# PWR_MCU.net
KiCad netlist of a schematic drawn in Altium Designer
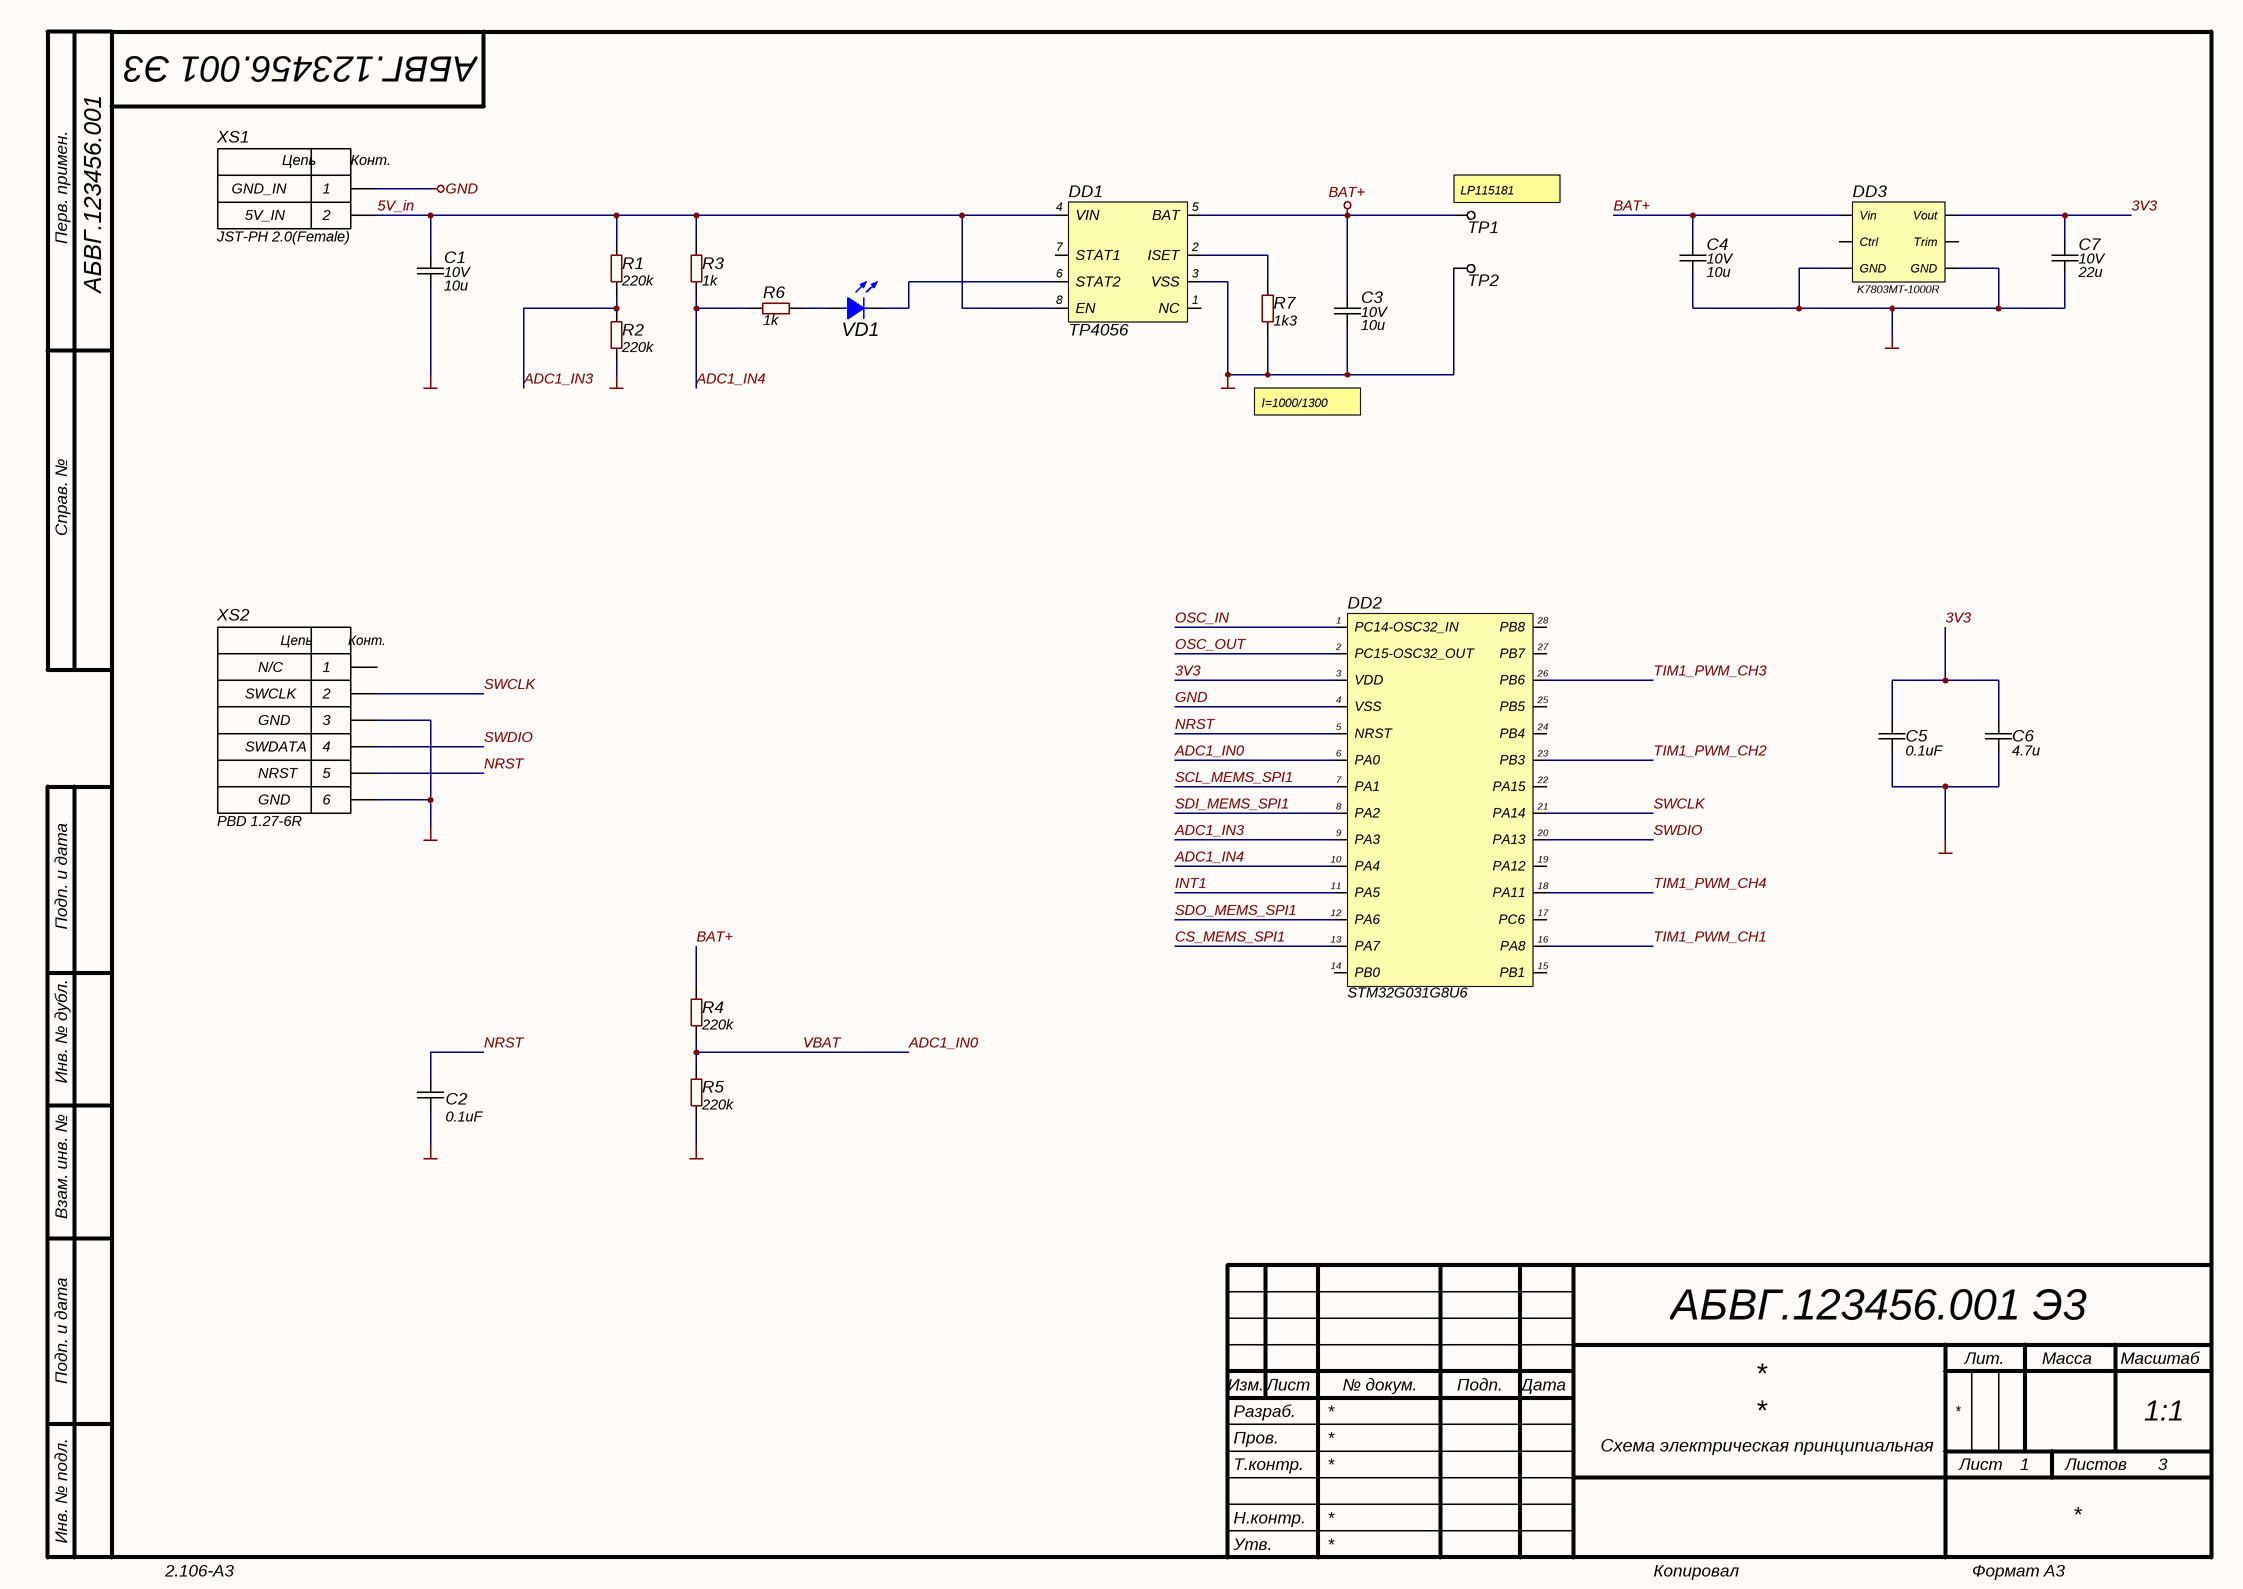
[diagram p0: PWR_MCU.SchDoc]

(export (version "E")
  (design (tool "Eeschema 10.0.6"))
  (components
    (comp (ref "C1")
      (value "10u")
      (footprint "CAP: 0603")
      (description "Capacitor")
      (fields
        (field (name "MANUFACTURER") "Yageo")
        (field (name "PARTNUMBER") "CC0603KRX7R7BB104")
        (field (name "VOLTAGE") "10V")
      )
      (libsource (lib "capacitor") (part "Ceramic_0603"))
    )
    (comp (ref "C2")
      (value "0.1uF")
      (footprint "CAP: 0603")
      (fields
        (field (name "MANUFACTURER") "Yageo")
        (field (name "PARTNUMBER") "CC0603KRX7R7BB104")
        (field (name "VALUEMANUFACTURERPARTNUMBER") "Ceramic capacitor, 0.1uF, X7R, ±10%, 16V, 0603, -55...+125°C")
      )
      (libsource (lib "capacitor") (part "Ceramic_0603"))
    )
    (comp (ref "C3")
      (value "10u")
      (footprint "CAP: 0603")
      (description "Capacitor")
      (fields
        (field (name "MANUFACTURER") "Yageo")
        (field (name "PARTNUMBER") "CC0603KRX7R7BB104")
        (field (name "VOLTAGE") "10V")
      )
      (libsource (lib "capacitor") (part "Ceramic_0603"))
    )
    (comp (ref "C4")
      (value "10u")
      (footprint "CAP: 0603")
      (description "Capacitor")
      (fields
        (field (name "MANUFACTURER") "Yageo")
        (field (name "PARTNUMBER") "CC0603KRX7R7BB104")
        (field (name "VOLTAGE") "10V")
      )
      (libsource (lib "capacitor") (part "Ceramic_0603"))
    )
    (comp (ref "C5")
      (value "0.1uF")
      (footprint "CAP: 0603")
      (fields
        (field (name "MANUFACTURER") "Yageo")
        (field (name "PARTNUMBER") "CC0603KRX7R7BB104")
        (field (name "VALUEMANUFACTURERPARTNUMBER") "Ceramic capacitor, 0.1uF, X7R, ±10%, 16V, 0603, -55...+125°C")
      )
      (libsource (lib "capacitor") (part "Ceramic_0603"))
    )
    (comp (ref "C6")
      (value "4.7u")
      (footprint "CAP: 0603")
      (fields
        (field (name "MANUFACTURER") "Yageo")
        (field (name "PARTNUMBER") "CC0603KRX7R7BB104")
        (field (name "VALUEMANUFACTURERPARTNUMBER") "Ceramic capacitor, 4.7u, X7R, ±10%, 16V, 0603, -55...+125°C")
      )
      (libsource (lib "capacitor") (part "Ceramic_0603"))
    )
    (comp (ref "C7")
      (value "22u")
      (footprint "CAP: 0603")
      (description "Capacitor")
      (fields
        (field (name "MANUFACTURER") "Yageo")
        (field (name "PARTNUMBER") "CC0603KRX7R7BB104")
        (field (name "VOLTAGE") "10V")
      )
      (libsource (lib "capacitor") (part "Ceramic_0603"))
    )
    (comp (ref "DD1")
      (value "TP4056")
      (footprint "8-ESOP")
      (description "Linear Li-Ion Battery Charger")
      (libsource (lib "ic-power-supply") (part "TP4056"))
    )
    (comp (ref "DD2")
      (value "STM32G031G8U6")
      (footprint "28-UFQFPN")
      (description "Cortex-M0+")
      (libsource (lib "ic-mcu") (part "STM32G031G8U6"))
    )
    (comp (ref "DD3")
      (value "K7803MT-1000R")
      (footprint "DFN_K7805")
      (description "DC/DC converter")
      (libsource (lib "ic-power-supply") (part "K7805MT-500R"))
    )
    (comp (ref "R1")
      (value "220k")
      (footprint "RES: 0603")
      (fields
        (field (name "MANUFACTURER") "Yageo")
        (field (name "PARTNUMBER") "RC0603JR-07100RL")
        (field (name "VALUEMANUFACTURERPARTNUMBER") "Resistor film, 220k, , 0603, 0.1W, -55...+125°C")
      )
      (libsource (lib "resistor") (part "Resistor_0603"))
    )
    (comp (ref "R2")
      (value "220k")
      (footprint "RES: 0603")
      (fields
        (field (name "MANUFACTURER") "Yageo")
        (field (name "PARTNUMBER") "RC0603JR-07100RL")
        (field (name "VALUEMANUFACTURERPARTNUMBER") "Resistor film, 220k, , 0603, 0.1W, -55...+125°C")
      )
      (libsource (lib "") (part "Resistor_0603_2"))
    )
    (comp (ref "R3")
      (value "1k")
      (footprint "RES: 0603")
      (fields
        (field (name "MANUFACTURER") "Yageo")
        (field (name "PARTNUMBER") "RC0603JR-07100RL")
        (field (name "VALUEMANUFACTURERPARTNUMBER") "Resistor film, 1k, , 0603, 0.1W, -55...+125°C")
      )
      (libsource (lib "resistor") (part "Resistor_0603"))
    )
    (comp (ref "R4")
      (value "220k")
      (footprint "RES: 0603")
      (fields
        (field (name "MANUFACTURER") "Yageo")
        (field (name "PARTNUMBER") "RC0603JR-07100RL")
        (field (name "VALUEMANUFACTURERPARTNUMBER") "Resistor film, 220k, , 0603, 0.1W, -55...+125°C")
      )
      (libsource (lib "resistor") (part "Resistor_0603"))
    )
    (comp (ref "R5")
      (value "220k")
      (footprint "RES: 0603")
      (fields
        (field (name "MANUFACTURER") "Yageo")
        (field (name "PARTNUMBER") "RC0603JR-07100RL")
        (field (name "VALUEMANUFACTURERPARTNUMBER") "Resistor film, 220k, , 0603, 0.1W, -55...+125°C")
      )
      (libsource (lib "resistor") (part "Resistor_0603"))
    )
    (comp (ref "R6")
      (value "1k")
      (footprint "RES: 0603")
      (fields
        (field (name "MANUFACTURER") "Yageo")
        (field (name "PARTNUMBER") "RC0603JR-07100RL")
        (field (name "VALUEMANUFACTURERPARTNUMBER") "Resistor film, 1k, , 0603, 0.1W, -55...+125°C")
      )
      (libsource (lib "") (part "Resistor_0603_1"))
    )
    (comp (ref "R7")
      (value "1k3")
      (footprint "RES: 0603")
      (fields
        (field (name "MANUFACTURER") "Yageo")
        (field (name "PARTNUMBER") "RC0603JR-07100RL")
        (field (name "VALUEMANUFACTURERPARTNUMBER") "Resistor film, 1k3, , 0603, 0.1W, -55...+125°C")
      )
      (libsource (lib "resistor") (part "Resistor_0603"))
    )
    (comp (ref "TP1")
      (value "Testpoint_HS1mm")
      (footprint "TestPoint(without 3D)")
      (libsource (lib "connector") (part "Testpoint_HS1mm"))
    )
    (comp (ref "TP2")
      (value "Testpoint_HS1mm")
      (footprint "TestPoint(without 3D)")
      (libsource (lib "connector") (part "Testpoint_HS1mm"))
    )
    (comp (ref "VD1")
      (value "~")
      (footprint "LED: 0603R")
      (fields (field (name "VALUEMANUFACTURERPARTNUMBER") "LED, Green, *, *, *, -55...+150°C"))
      (libsource (lib "diode") (part "LED_single"))
    )
    (comp (ref "XS1")
      (value "JST-PH 2.0(Female)")
      (footprint "JST-PH 2.0(Female)")
      (libsource (lib "connector") (part "JST-PH 2.0(Female)"))
    )
    (comp (ref "XS2")
      (value "PBD 1.27-6R")
      (footprint "CON: PLLD-6R(1.27)")
      (description "DS1065-14-2X3S8BR")
      (libsource (lib "connector") (part "PBD 1.27-6R"))
    )
  )
  (nets
    (net (code "1") (name "/3V3") (class "Default")
      (node (ref "C5") (pin "2") (pinfunction "2_2") (pintype "passive"))
      (node (ref "C6") (pin "2") (pinfunction "2_2") (pintype "passive"))
      (node (ref "C7") (pin "2") (pinfunction "2_2") (pintype "passive"))
      (node (ref "DD2") (pin "3") (pinfunction "VDD_3") (pintype "passive"))
      (node (ref "DD3") (pin "3") (pinfunction "Vout_3") (pintype "passive"))
    )
    (net (code "2") (name "/5V_in") (class "Default")
      (node (ref "C1") (pin "2") (pinfunction "2_2") (pintype "passive"))
      (node (ref "DD1") (pin "4") (pinfunction "VIN_4") (pintype "passive"))
      (node (ref "DD1") (pin "8") (pinfunction "EN_8") (pintype "passive"))
      (node (ref "R1") (pin "2") (pinfunction "2_2") (pintype "passive"))
      (node (ref "R3") (pin "2") (pinfunction "2_2") (pintype "passive"))
      (node (ref "XS1") (pin "2") (pinfunction "2_2") (pintype "passive"))
    )
    (net (code "3") (name "/ADC1_IN0") (class "Default")
      (node (ref "DD2") (pin "6") (pinfunction "PA0_6") (pintype "passive"))
      (node (ref "R4") (pin "1") (pinfunction "1_1") (pintype "passive"))
      (node (ref "R5") (pin "2") (pinfunction "2_2") (pintype "passive"))
    )
    (net (code "4") (name "/ADC1_IN3") (class "Default")
      (node (ref "DD2") (pin "9") (pinfunction "PA3_9") (pintype "passive"))
      (node (ref "R1") (pin "1") (pinfunction "1_1") (pintype "passive"))
      (node (ref "R2") (pin "1") (pinfunction "1_1") (pintype "passive"))
    )
    (net (code "5") (name "/ADC1_IN4") (class "Default")
      (node (ref "DD2") (pin "10") (pinfunction "PA4_10") (pintype "passive"))
      (node (ref "R3") (pin "1") (pinfunction "1_1") (pintype "passive"))
      (node (ref "R6") (pin "2") (pinfunction "2_2") (pintype "passive"))
    )
    (net (code "6") (name "/CS_MEMS_SPI1") (class "Default")
      (node (ref "DD2") (pin "13") (pinfunction "PA7_13") (pintype "passive"))
    )
    (net (code "7") (name "/INT1") (class "Default")
      (node (ref "DD2") (pin "11") (pinfunction "PA5_11") (pintype "passive"))
    )
    (net (code "8") (name "/NRST") (class "Default")
      (node (ref "C2") (pin "2") (pinfunction "2_2") (pintype "passive"))
      (node (ref "DD2") (pin "5") (pinfunction "NRST_5") (pintype "passive"))
      (node (ref "XS2") (pin "5") (pinfunction "5_5") (pintype "passive"))
    )
    (net (code "9") (name "/OSC_IN") (class "Default")
      (node (ref "DD2") (pin "1") (pinfunction "PC14-OSC32_IN_1") (pintype "passive"))
    )
    (net (code "10") (name "/OSC_OUT") (class "Default")
      (node (ref "DD2") (pin "2") (pinfunction "PC15-OSC32_OUT_2") (pintype "passive"))
    )
    (net (code "11") (name "/SCL_MEMS_SPI1") (class "Default")
      (node (ref "DD2") (pin "7") (pinfunction "PA1_7") (pintype "passive"))
    )
    (net (code "12") (name "/SDI_MEMS_SPI1") (class "Default")
      (node (ref "DD2") (pin "8") (pinfunction "PA2_8") (pintype "passive"))
    )
    (net (code "13") (name "/SDO_MEMS_SPI1") (class "Default")
      (node (ref "DD2") (pin "12") (pinfunction "PA6_12") (pintype "passive"))
    )
    (net (code "14") (name "/SWCLK") (class "Default")
      (node (ref "DD2") (pin "21") (pinfunction "PA14_21") (pintype "passive"))
      (node (ref "XS2") (pin "2") (pinfunction "2_2") (pintype "passive"))
    )
    (net (code "15") (name "/SWDIO") (class "Default")
      (node (ref "DD2") (pin "20") (pinfunction "PA13_20") (pintype "passive"))
      (node (ref "XS2") (pin "4") (pinfunction "4_4") (pintype "passive"))
    )
    (net (code "16") (name "/TIM1_PWM_CH1") (class "Default")
      (node (ref "DD2") (pin "16") (pinfunction "PA8_16") (pintype "passive"))
    )
    (net (code "17") (name "/TIM1_PWM_CH2") (class "Default")
      (node (ref "DD2") (pin "23") (pinfunction "PB3_23") (pintype "passive"))
    )
    (net (code "18") (name "/TIM1_PWM_CH3") (class "Default")
      (node (ref "DD2") (pin "26") (pinfunction "PB6_26") (pintype "passive"))
    )
    (net (code "19") (name "/TIM1_PWM_CH4") (class "Default")
      (node (ref "DD2") (pin "18") (pinfunction "PA11_18") (pintype "passive"))
    )
    (net (code "20") (name "BAT+") (class "Default")
      (node (ref "C3") (pin "2") (pinfunction "2_2") (pintype "passive"))
      (node (ref "C4") (pin "2") (pinfunction "2_2") (pintype "passive"))
      (node (ref "DD1") (pin "5") (pinfunction "BAT_5") (pintype "passive"))
      (node (ref "DD3") (pin "1") (pinfunction "Vin_1") (pintype "passive"))
      (node (ref "R4") (pin "2") (pinfunction "2_2") (pintype "passive"))
      (node (ref "TP1") (pin "1") (pinfunction "1_1") (pintype "passive"))
    )
    (net (code "21") (name "GND") (class "Default")
      (node (ref "C1") (pin "1") (pinfunction "1_1") (pintype "passive"))
      (node (ref "C2") (pin "1") (pinfunction "1_1") (pintype "passive"))
      (node (ref "C3") (pin "1") (pinfunction "1_1") (pintype "passive"))
      (node (ref "C4") (pin "1") (pinfunction "1_1") (pintype "passive"))
      (node (ref "C5") (pin "1") (pinfunction "1_1") (pintype "passive"))
      (node (ref "C6") (pin "1") (pinfunction "1_1") (pintype "passive"))
      (node (ref "C7") (pin "1") (pinfunction "1_1") (pintype "passive"))
      (node (ref "DD1") (pin "3") (pinfunction "VSS_3") (pintype "passive"))
      (node (ref "DD2") (pin "4") (pinfunction "VSS_4") (pintype "passive"))
      (node (ref "DD3") (pin "2") (pinfunction "GND_2") (pintype "passive"))
      (node (ref "DD3") (pin "5") (pinfunction "GND_5") (pintype "passive"))
      (node (ref "R2") (pin "2") (pinfunction "2_2") (pintype "passive"))
      (node (ref "R5") (pin "1") (pinfunction "1_1") (pintype "passive"))
      (node (ref "R7") (pin "1") (pinfunction "1_1") (pintype "passive"))
      (node (ref "TP2") (pin "1") (pinfunction "1_1") (pintype "passive"))
      (node (ref "XS1") (pin "1") (pinfunction "1_1") (pintype "passive"))
      (node (ref "XS2") (pin "3") (pinfunction "3_3") (pintype "passive"))
      (node (ref "XS2") (pin "6") (pinfunction "6_6") (pintype "passive"))
    )
    (net (code "22") (name "Net-(DD1-ISET)") (class "Default")
      (node (ref "DD1") (pin "2") (pinfunction "ISET_2") (pintype "passive"))
      (node (ref "R7") (pin "2") (pinfunction "2_2") (pintype "passive"))
    )
    (net (code "23") (name "Net-(DD1-STAT2)") (class "Default")
      (node (ref "DD1") (pin "6") (pinfunction "STAT2_6") (pintype "passive"))
      (node (ref "VD1") (pin "2") (pinfunction "C_2") (pintype "passive"))
    )
    (net (code "24") (name "Net-(VD1-A)") (class "Default")
      (node (ref "R6") (pin "1") (pinfunction "1_1") (pintype "passive"))
      (node (ref "VD1") (pin "1") (pinfunction "A_1") (pintype "passive"))
    )
    (net (code "25") (name "unconnected-(DD1-NC-Pad1)") (class "Default")
      (node (ref "DD1") (pin "1") (pinfunction "NC_1") (pintype "passive"))
    )
    (net (code "26") (name "unconnected-(DD1-STAT1-Pad7)") (class "Default")
      (node (ref "DD1") (pin "7") (pinfunction "STAT1_7") (pintype "passive"))
    )
    (net (code "27") (name "unconnected-(DD2-PA12-Pad19)") (class "Default")
      (node (ref "DD2") (pin "19") (pinfunction "PA12_19") (pintype "passive"))
    )
    (net (code "28") (name "unconnected-(DD2-PA15-Pad22)") (class "Default")
      (node (ref "DD2") (pin "22") (pinfunction "PA15_22") (pintype "passive"))
    )
    (net (code "29") (name "unconnected-(DD2-PB0-Pad14)") (class "Default")
      (node (ref "DD2") (pin "14") (pinfunction "PB0_14") (pintype "passive"))
    )
    (net (code "30") (name "unconnected-(DD2-PB1-Pad15)") (class "Default")
      (node (ref "DD2") (pin "15") (pinfunction "PB1_15") (pintype "passive"))
    )
    (net (code "31") (name "unconnected-(DD2-PB4-Pad24)") (class "Default")
      (node (ref "DD2") (pin "24") (pinfunction "PB4_24") (pintype "passive"))
    )
    (net (code "32") (name "unconnected-(DD2-PB5-Pad25)") (class "Default")
      (node (ref "DD2") (pin "25") (pinfunction "PB5_25") (pintype "passive"))
    )
    (net (code "33") (name "unconnected-(DD2-PB7-Pad27)") (class "Default")
      (node (ref "DD2") (pin "27") (pinfunction "PB7_27") (pintype "passive"))
    )
    (net (code "34") (name "unconnected-(DD2-PB8-Pad28)") (class "Default")
      (node (ref "DD2") (pin "28") (pinfunction "PB8_28") (pintype "passive"))
    )
    (net (code "35") (name "unconnected-(DD2-PC6-Pad17)") (class "Default")
      (node (ref "DD2") (pin "17") (pinfunction "PC6_17") (pintype "passive"))
    )
    (net (code "36") (name "unconnected-(DD3-Ctrl-Pad6)") (class "Default")
      (node (ref "DD3") (pin "6") (pinfunction "Ctrl_6") (pintype "passive"))
    )
    (net (code "37") (name "unconnected-(DD3-Trim-Pad4)") (class "Default")
      (node (ref "DD3") (pin "4") (pinfunction "Trim_4") (pintype "passive"))
    )
    (net (code "38") (name "unconnected-(XS2-Pad1)") (class "Default")
      (node (ref "XS2") (pin "1") (pinfunction "1_1") (pintype "passive"))
    )
  )
)
